# PotBreakout.net
KiCad netlist of a schematic drawn in EAGLE
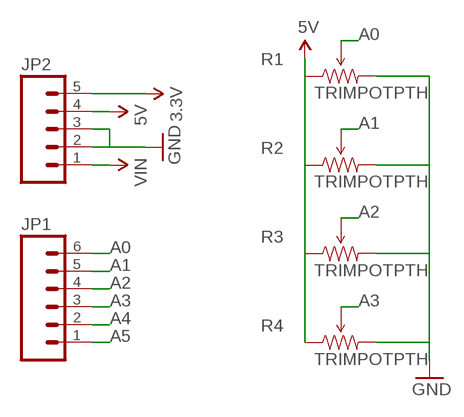
[diagram p0: schematic, sheet 1]

(export (version "E")
  (design (tool "Eeschema 10.0.6"))
  (components
    (comp (ref "JP1")
      (value "M06SIP")
      (footprint "eagle-import:1X06")
      (libsource (lib "eagle-import") (part "M06SIP"))
    )
    (comp (ref "JP2")
      (value "M05NO_SILK")
      (footprint "eagle-import:1X05_NO_SILK")
      (libsource (lib "eagle-import") (part "M05NO_SILK"))
    )
    (comp (ref "R1")
      (value "TRIMPOTPTH")
      (footprint "eagle-import:TRIM_POT_PTH")
      (libsource (lib "eagle-import") (part "TRIMPOTPTH"))
    )
    (comp (ref "R2")
      (value "TRIMPOTPTH")
      (footprint "eagle-import:TRIM_POT_PTH")
      (libsource (lib "eagle-import") (part "TRIMPOTPTH"))
    )
    (comp (ref "R3")
      (value "TRIMPOTPTH")
      (footprint "eagle-import:TRIM_POT_PTH")
      (libsource (lib "eagle-import") (part "TRIMPOTPTH"))
    )
    (comp (ref "R4")
      (value "TRIMPOTPTH")
      (footprint "eagle-import:TRIM_POT_PTH")
      (libsource (lib "eagle-import") (part "TRIMPOTPTH"))
    )
  )
  (nets
    (net (code "1") (name "/A0") (class "Default")
      (node (ref "JP1") (pin "6") (pinfunction "6_6") (pintype "passive"))
      (node (ref "R1") (pin "2") (pinfunction "WIPER_2") (pintype "passive"))
    )
    (net (code "2") (name "/A1") (class "Default")
      (node (ref "JP1") (pin "5") (pinfunction "5_5") (pintype "passive"))
      (node (ref "R2") (pin "2") (pinfunction "WIPER_2") (pintype "passive"))
    )
    (net (code "3") (name "/A2") (class "Default")
      (node (ref "JP1") (pin "4") (pinfunction "4_4") (pintype "passive"))
      (node (ref "R3") (pin "2") (pinfunction "WIPER_2") (pintype "passive"))
    )
    (net (code "4") (name "/A3") (class "Default")
      (node (ref "JP1") (pin "3") (pinfunction "3_3") (pintype "passive"))
      (node (ref "R4") (pin "2") (pinfunction "WIPER_2") (pintype "passive"))
    )
    (net (code "5") (name "/A4") (class "Default")
      (node (ref "JP1") (pin "2") (pinfunction "2_2") (pintype "passive"))
    )
    (net (code "6") (name "/A5") (class "Default")
      (node (ref "JP1") (pin "1") (pinfunction "1_1") (pintype "passive"))
    )
    (net (code "7") (name "3.3V") (class "Default")
      (node (ref "JP2") (pin "5") (pinfunction "5_5") (pintype "passive"))
    )
    (net (code "8") (name "5V") (class "Default")
      (node (ref "JP2") (pin "4") (pinfunction "4_4") (pintype "passive"))
      (node (ref "R1") (pin "1") (pinfunction "CCW_1") (pintype "passive"))
      (node (ref "R2") (pin "1") (pinfunction "CCW_1") (pintype "passive"))
      (node (ref "R3") (pin "1") (pinfunction "CCW_1") (pintype "passive"))
      (node (ref "R4") (pin "1") (pinfunction "CCW_1") (pintype "passive"))
    )
    (net (code "9") (name "GND") (class "Default")
      (node (ref "JP2") (pin "2") (pinfunction "2_2") (pintype "passive"))
      (node (ref "JP2") (pin "3") (pinfunction "3_3") (pintype "passive"))
      (node (ref "R1") (pin "3") (pinfunction "CW_3") (pintype "passive"))
      (node (ref "R2") (pin "3") (pinfunction "CW_3") (pintype "passive"))
      (node (ref "R3") (pin "3") (pinfunction "CW_3") (pintype "passive"))
      (node (ref "R4") (pin "3") (pinfunction "CW_3") (pintype "passive"))
    )
    (net (code "10") (name "VIN") (class "Default")
      (node (ref "JP2") (pin "1") (pinfunction "1_1") (pintype "passive"))
    )
  )
)
